# APCBaby8_UIBoard.net
KiCad netlist of a schematic drawn in EAGLE
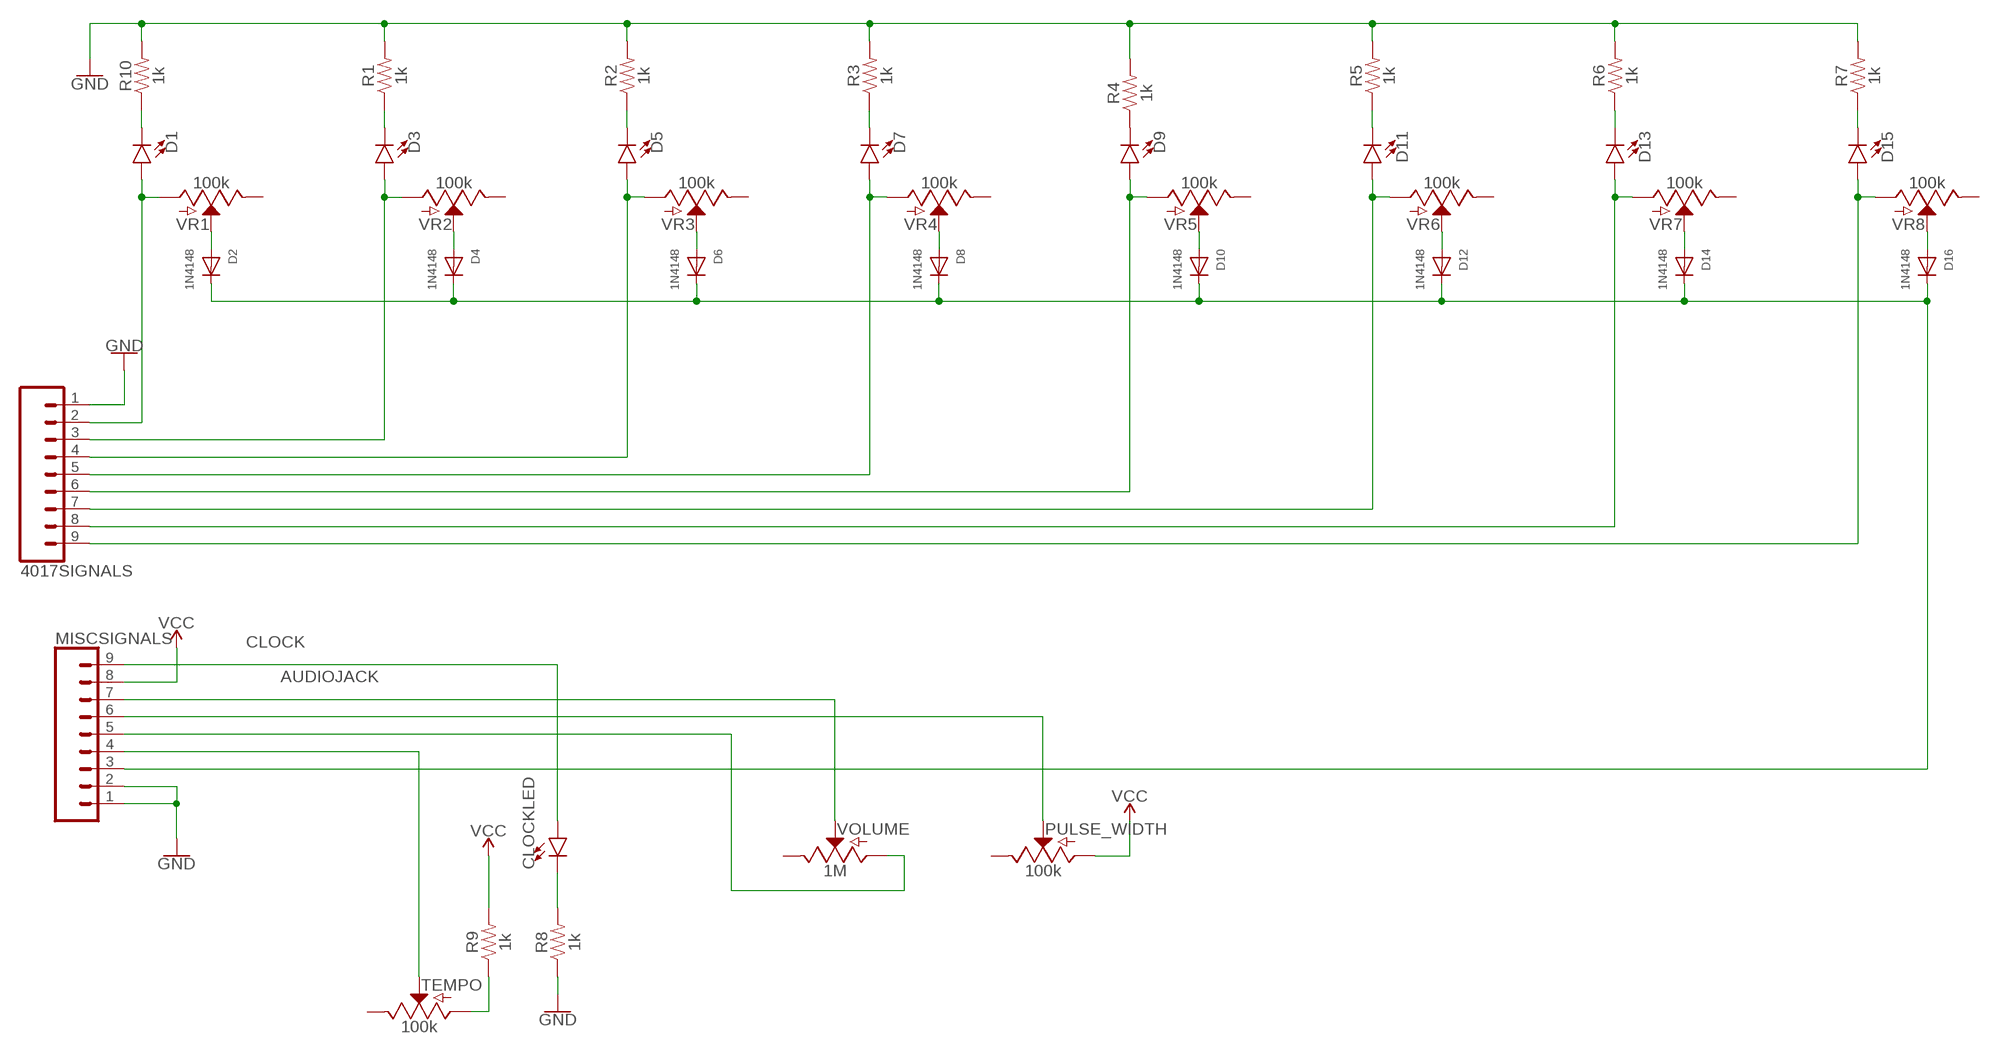
[diagram p0: schematic, sheet 1]

(export (version "E")
  (design (tool "Eeschema 10.0.6"))
  (components
    (comp (ref "4017SIGNALS")
      (value "CONN_09LONGPADS")
      (footprint "eagle-import:1X09_LONGPADS")
      (libsource (lib "eagle-import") (part "CONN_09LONGPADS"))
    )
    (comp (ref "CLOCKLED")
      (value "LED-3MM-NO_SILK")
      (footprint "eagle-import:LED_3MM-NS")
      (libsource (lib "eagle-import") (part "LED-3MM-NO_SILK"))
    )
    (comp (ref "D1")
      (value "LED-3MM-NO_SILK")
      (footprint "eagle-import:LED_3MM-NS")
      (libsource (lib "eagle-import") (part "LED-3MM-NO_SILK"))
    )
    (comp (ref "D2")
      (value "1N4148")
      (footprint "eagle-import:DO-1N4148")
      (libsource (lib "eagle-import") (part "DIODEDO-1N4148"))
    )
    (comp (ref "D3")
      (value "LED-3MM-NO_SILK")
      (footprint "eagle-import:LED_3MM-NS")
      (libsource (lib "eagle-import") (part "LED-3MM-NO_SILK"))
    )
    (comp (ref "D4")
      (value "1N4148")
      (footprint "eagle-import:DO-1N4148")
      (libsource (lib "eagle-import") (part "DIODEDO-1N4148"))
    )
    (comp (ref "D5")
      (value "LED-3MM-NO_SILK")
      (footprint "eagle-import:LED_3MM-NS")
      (libsource (lib "eagle-import") (part "LED-3MM-NO_SILK"))
    )
    (comp (ref "D6")
      (value "1N4148")
      (footprint "eagle-import:DO-1N4148")
      (libsource (lib "eagle-import") (part "DIODEDO-1N4148"))
    )
    (comp (ref "D7")
      (value "LED-3MM-NO_SILK")
      (footprint "eagle-import:LED_3MM-NS")
      (libsource (lib "eagle-import") (part "LED-3MM-NO_SILK"))
    )
    (comp (ref "D8")
      (value "1N4148")
      (footprint "eagle-import:DO-1N4148")
      (libsource (lib "eagle-import") (part "DIODEDO-1N4148"))
    )
    (comp (ref "D9")
      (value "LED-3MM-NO_SILK")
      (footprint "eagle-import:LED_3MM-NS")
      (libsource (lib "eagle-import") (part "LED-3MM-NO_SILK"))
    )
    (comp (ref "D10")
      (value "1N4148")
      (footprint "eagle-import:DO-1N4148")
      (libsource (lib "eagle-import") (part "DIODEDO-1N4148"))
    )
    (comp (ref "D11")
      (value "LED-3MM-NO_SILK")
      (footprint "eagle-import:LED_3MM-NS")
      (libsource (lib "eagle-import") (part "LED-3MM-NO_SILK"))
    )
    (comp (ref "D12")
      (value "1N4148")
      (footprint "eagle-import:DO-1N4148")
      (libsource (lib "eagle-import") (part "DIODEDO-1N4148"))
    )
    (comp (ref "D13")
      (value "LED-3MM-NO_SILK")
      (footprint "eagle-import:LED_3MM-NS")
      (libsource (lib "eagle-import") (part "LED-3MM-NO_SILK"))
    )
    (comp (ref "D14")
      (value "1N4148")
      (footprint "eagle-import:DO-1N4148")
      (libsource (lib "eagle-import") (part "DIODEDO-1N4148"))
    )
    (comp (ref "D15")
      (value "LED-3MM-NO_SILK")
      (footprint "eagle-import:LED_3MM-NS")
      (libsource (lib "eagle-import") (part "LED-3MM-NO_SILK"))
    )
    (comp (ref "D16")
      (value "1N4148")
      (footprint "eagle-import:DO-1N4148")
      (libsource (lib "eagle-import") (part "DIODEDO-1N4148"))
    )
    (comp (ref "MISCSIGNALS")
      (value "CONN_09LONGPADS")
      (footprint "eagle-import:1X09_LONGPADS")
      (libsource (lib "eagle-import") (part "CONN_09LONGPADS"))
    )
    (comp (ref "PULSE_WIDTH")
      (value "100k")
      (footprint "eagle-import:POT-PTH-ALPS")
      (libsource (lib "eagle-import") (part "POTENTIOMETER-PTH-9MM-1/20W-20%"))
    )
    (comp (ref "R1")
      (value "1k")
      (footprint "eagle-import:0805")
      (libsource (lib "eagle-import") (part "0.22OHM-0805-1/4W-1%"))
    )
    (comp (ref "R2")
      (value "1k")
      (footprint "eagle-import:0805")
      (libsource (lib "eagle-import") (part "0.22OHM-0805-1/4W-1%"))
    )
    (comp (ref "R3")
      (value "1k")
      (footprint "eagle-import:0805")
      (libsource (lib "eagle-import") (part "0.22OHM-0805-1/4W-1%"))
    )
    (comp (ref "R4")
      (value "1k")
      (footprint "eagle-import:0805")
      (libsource (lib "eagle-import") (part "0.22OHM-0805-1/4W-1%"))
    )
    (comp (ref "R5")
      (value "1k")
      (footprint "eagle-import:0805")
      (libsource (lib "eagle-import") (part "0.22OHM-0805-1/4W-1%"))
    )
    (comp (ref "R6")
      (value "1k")
      (footprint "eagle-import:0805")
      (libsource (lib "eagle-import") (part "0.22OHM-0805-1/4W-1%"))
    )
    (comp (ref "R7")
      (value "1k")
      (footprint "eagle-import:0805")
      (libsource (lib "eagle-import") (part "0.22OHM-0805-1/4W-1%"))
    )
    (comp (ref "R8")
      (value "1k")
      (footprint "eagle-import:0805")
      (libsource (lib "eagle-import") (part "0.22OHM-0805-1/4W-1%"))
    )
    (comp (ref "R9")
      (value "1k")
      (footprint "eagle-import:0805")
      (libsource (lib "eagle-import") (part "0.22OHM-0805-1/4W-1%"))
    )
    (comp (ref "R10")
      (value "1k")
      (footprint "eagle-import:0805")
      (libsource (lib "eagle-import") (part "0.22OHM-0805-1/4W-1%"))
    )
    (comp (ref "TEMPO")
      (value "100k")
      (footprint "eagle-import:POT-PTH-ALPS")
      (libsource (lib "eagle-import") (part "POTENTIOMETER-PTH-9MM-1/20W-20%"))
    )
    (comp (ref "VOLUME")
      (value "1M")
      (footprint "eagle-import:POT-PTH-ALPS")
      (libsource (lib "eagle-import") (part "POTENTIOMETER-PTH-9MM-1/20W-20%"))
    )
    (comp (ref "VR1")
      (value "100k")
      (footprint "eagle-import:POT-PTH-ALPS")
      (libsource (lib "eagle-import") (part "POTENTIOMETER-PTH-9MM-1/20W-20%"))
    )
    (comp (ref "VR2")
      (value "100k")
      (footprint "eagle-import:POT-PTH-ALPS")
      (libsource (lib "eagle-import") (part "POTENTIOMETER-PTH-9MM-1/20W-20%"))
    )
    (comp (ref "VR3")
      (value "100k")
      (footprint "eagle-import:POT-PTH-ALPS")
      (libsource (lib "eagle-import") (part "POTENTIOMETER-PTH-9MM-1/20W-20%"))
    )
    (comp (ref "VR4")
      (value "100k")
      (footprint "eagle-import:POT-PTH-ALPS")
      (libsource (lib "eagle-import") (part "POTENTIOMETER-PTH-9MM-1/20W-20%"))
    )
    (comp (ref "VR5")
      (value "100k")
      (footprint "eagle-import:POT-PTH-ALPS")
      (libsource (lib "eagle-import") (part "POTENTIOMETER-PTH-9MM-1/20W-20%"))
    )
    (comp (ref "VR6")
      (value "100k")
      (footprint "eagle-import:POT-PTH-ALPS")
      (libsource (lib "eagle-import") (part "POTENTIOMETER-PTH-9MM-1/20W-20%"))
    )
    (comp (ref "VR7")
      (value "100k")
      (footprint "eagle-import:POT-PTH-ALPS")
      (libsource (lib "eagle-import") (part "POTENTIOMETER-PTH-9MM-1/20W-20%"))
    )
    (comp (ref "VR8")
      (value "100k")
      (footprint "eagle-import:POT-PTH-ALPS")
      (libsource (lib "eagle-import") (part "POTENTIOMETER-PTH-9MM-1/20W-20%"))
    )
  )
  (nets
    (net (code "1") (name "/AUDIOJACK") (class "Default")
      (node (ref "MISCSIGNALS") (pin "7") (pinfunction "7_7") (pintype "passive"))
      (node (ref "VOLUME") (pin "P$2") (pinfunction "S_P$2") (pintype "passive"))
    )
    (net (code "2") (name "/CLOCK") (class "Default")
      (node (ref "CLOCKLED") (pin "A") (pinfunction "A_A") (pintype "passive"))
      (node (ref "MISCSIGNALS") (pin "9") (pinfunction "9_9") (pintype "passive"))
    )
    (net (code "3") (name "GND") (class "Default")
      (node (ref "4017SIGNALS") (pin "1") (pinfunction "1_1") (pintype "passive"))
      (node (ref "MISCSIGNALS") (pin "1") (pinfunction "1_1") (pintype "passive"))
      (node (ref "MISCSIGNALS") (pin "2") (pinfunction "2_2") (pintype "passive"))
      (node (ref "R1") (pin "2") (pinfunction "2_2") (pintype "passive"))
      (node (ref "R10") (pin "2") (pinfunction "2_2") (pintype "passive"))
      (node (ref "R2") (pin "2") (pinfunction "2_2") (pintype "passive"))
      (node (ref "R3") (pin "2") (pinfunction "2_2") (pintype "passive"))
      (node (ref "R4") (pin "2") (pinfunction "2_2") (pintype "passive"))
      (node (ref "R5") (pin "2") (pinfunction "2_2") (pintype "passive"))
      (node (ref "R6") (pin "2") (pinfunction "2_2") (pintype "passive"))
      (node (ref "R7") (pin "2") (pinfunction "2_2") (pintype "passive"))
      (node (ref "R8") (pin "1") (pinfunction "1_1") (pintype "passive"))
    )
    (net (code "4") (name "Net-(CLOCKLED-C)") (class "Default")
      (node (ref "CLOCKLED") (pin "K") (pinfunction "C_K") (pintype "passive"))
      (node (ref "R8") (pin "2") (pinfunction "2_2") (pintype "passive"))
    )
    (net (code "5") (name "Net-(D1-C)") (class "Default")
      (node (ref "D1") (pin "K") (pinfunction "C_K") (pintype "passive"))
      (node (ref "R10") (pin "1") (pinfunction "1_1") (pintype "passive"))
    )
    (net (code "6") (name "Net-(D3-C)") (class "Default")
      (node (ref "D3") (pin "K") (pinfunction "C_K") (pintype "passive"))
      (node (ref "R1") (pin "1") (pinfunction "1_1") (pintype "passive"))
    )
    (net (code "7") (name "Net-(D5-C)") (class "Default")
      (node (ref "D5") (pin "K") (pinfunction "C_K") (pintype "passive"))
      (node (ref "R2") (pin "1") (pinfunction "1_1") (pintype "passive"))
    )
    (net (code "8") (name "Net-(D7-C)") (class "Default")
      (node (ref "D7") (pin "K") (pinfunction "C_K") (pintype "passive"))
      (node (ref "R3") (pin "1") (pinfunction "1_1") (pintype "passive"))
    )
    (net (code "9") (name "Net-(D9-C)") (class "Default")
      (node (ref "D9") (pin "K") (pinfunction "C_K") (pintype "passive"))
      (node (ref "R4") (pin "1") (pinfunction "1_1") (pintype "passive"))
    )
    (net (code "10") (name "Net-(D10-PadC)") (class "Default")
      (node (ref "D10") (pin "C") (pinfunction "C_C") (pintype "passive"))
      (node (ref "D12") (pin "C") (pinfunction "C_C") (pintype "passive"))
      (node (ref "D14") (pin "C") (pinfunction "C_C") (pintype "passive"))
      (node (ref "D16") (pin "C") (pinfunction "C_C") (pintype "passive"))
      (node (ref "D2") (pin "C") (pinfunction "C_C") (pintype "passive"))
      (node (ref "D4") (pin "C") (pinfunction "C_C") (pintype "passive"))
      (node (ref "D6") (pin "C") (pinfunction "C_C") (pintype "passive"))
      (node (ref "D8") (pin "C") (pinfunction "C_C") (pintype "passive"))
      (node (ref "MISCSIGNALS") (pin "3") (pinfunction "3_3") (pintype "passive"))
    )
    (net (code "11") (name "Net-(D11-C)") (class "Default")
      (node (ref "D11") (pin "K") (pinfunction "C_K") (pintype "passive"))
      (node (ref "R5") (pin "1") (pinfunction "1_1") (pintype "passive"))
    )
    (net (code "12") (name "Net-(D13-C)") (class "Default")
      (node (ref "D13") (pin "K") (pinfunction "C_K") (pintype "passive"))
      (node (ref "R6") (pin "1") (pinfunction "1_1") (pintype "passive"))
    )
    (net (code "13") (name "Net-(D15-C)") (class "Default")
      (node (ref "D15") (pin "K") (pinfunction "C_K") (pintype "passive"))
      (node (ref "R7") (pin "1") (pinfunction "1_1") (pintype "passive"))
    )
    (net (code "14") (name "Net-(PULSE_WIDTH-S)") (class "Default")
      (node (ref "MISCSIGNALS") (pin "6") (pinfunction "6_6") (pintype "passive"))
      (node (ref "PULSE_WIDTH") (pin "P$2") (pinfunction "S_P$2") (pintype "passive"))
    )
    (net (code "15") (name "Net-(TEMPO-A)") (class "Default")
      (node (ref "R9") (pin "1") (pinfunction "1_1") (pintype "passive"))
      (node (ref "TEMPO") (pin "P$3") (pinfunction "A_P$3") (pintype "passive"))
    )
    (net (code "16") (name "Net-(TEMPO-S)") (class "Default")
      (node (ref "MISCSIGNALS") (pin "4") (pinfunction "4_4") (pintype "passive"))
      (node (ref "TEMPO") (pin "P$2") (pinfunction "S_P$2") (pintype "passive"))
    )
    (net (code "17") (name "Net-(VOLUME-A)") (class "Default")
      (node (ref "MISCSIGNALS") (pin "5") (pinfunction "5_5") (pintype "passive"))
      (node (ref "VOLUME") (pin "P$3") (pinfunction "A_P$3") (pintype "passive"))
    )
    (net (code "18") (name "Net-(VR1-A)") (class "Default")
      (node (ref "4017SIGNALS") (pin "2") (pinfunction "2_2") (pintype "passive"))
      (node (ref "D1") (pin "A") (pinfunction "A_A") (pintype "passive"))
      (node (ref "VR1") (pin "P$3") (pinfunction "A_P$3") (pintype "passive"))
    )
    (net (code "19") (name "Net-(VR1-S)") (class "Default")
      (node (ref "D2") (pin "A") (pinfunction "A_A") (pintype "passive"))
      (node (ref "VR1") (pin "P$2") (pinfunction "S_P$2") (pintype "passive"))
    )
    (net (code "20") (name "Net-(VR2-A)") (class "Default")
      (node (ref "4017SIGNALS") (pin "3") (pinfunction "3_3") (pintype "passive"))
      (node (ref "D3") (pin "A") (pinfunction "A_A") (pintype "passive"))
      (node (ref "VR2") (pin "P$3") (pinfunction "A_P$3") (pintype "passive"))
    )
    (net (code "21") (name "Net-(VR2-S)") (class "Default")
      (node (ref "D4") (pin "A") (pinfunction "A_A") (pintype "passive"))
      (node (ref "VR2") (pin "P$2") (pinfunction "S_P$2") (pintype "passive"))
    )
    (net (code "22") (name "Net-(VR3-A)") (class "Default")
      (node (ref "4017SIGNALS") (pin "4") (pinfunction "4_4") (pintype "passive"))
      (node (ref "D5") (pin "A") (pinfunction "A_A") (pintype "passive"))
      (node (ref "VR3") (pin "P$3") (pinfunction "A_P$3") (pintype "passive"))
    )
    (net (code "23") (name "Net-(VR3-S)") (class "Default")
      (node (ref "D6") (pin "A") (pinfunction "A_A") (pintype "passive"))
      (node (ref "VR3") (pin "P$2") (pinfunction "S_P$2") (pintype "passive"))
    )
    (net (code "24") (name "Net-(VR4-A)") (class "Default")
      (node (ref "4017SIGNALS") (pin "5") (pinfunction "5_5") (pintype "passive"))
      (node (ref "D7") (pin "A") (pinfunction "A_A") (pintype "passive"))
      (node (ref "VR4") (pin "P$3") (pinfunction "A_P$3") (pintype "passive"))
    )
    (net (code "25") (name "Net-(VR4-S)") (class "Default")
      (node (ref "D8") (pin "A") (pinfunction "A_A") (pintype "passive"))
      (node (ref "VR4") (pin "P$2") (pinfunction "S_P$2") (pintype "passive"))
    )
    (net (code "26") (name "Net-(VR5-A)") (class "Default")
      (node (ref "4017SIGNALS") (pin "6") (pinfunction "6_6") (pintype "passive"))
      (node (ref "D9") (pin "A") (pinfunction "A_A") (pintype "passive"))
      (node (ref "VR5") (pin "P$3") (pinfunction "A_P$3") (pintype "passive"))
    )
    (net (code "27") (name "Net-(VR5-S)") (class "Default")
      (node (ref "D10") (pin "A") (pinfunction "A_A") (pintype "passive"))
      (node (ref "VR5") (pin "P$2") (pinfunction "S_P$2") (pintype "passive"))
    )
    (net (code "28") (name "Net-(VR6-A)") (class "Default")
      (node (ref "4017SIGNALS") (pin "7") (pinfunction "7_7") (pintype "passive"))
      (node (ref "D11") (pin "A") (pinfunction "A_A") (pintype "passive"))
      (node (ref "VR6") (pin "P$3") (pinfunction "A_P$3") (pintype "passive"))
    )
    (net (code "29") (name "Net-(VR6-S)") (class "Default")
      (node (ref "D12") (pin "A") (pinfunction "A_A") (pintype "passive"))
      (node (ref "VR6") (pin "P$2") (pinfunction "S_P$2") (pintype "passive"))
    )
    (net (code "30") (name "Net-(VR7-A)") (class "Default")
      (node (ref "4017SIGNALS") (pin "8") (pinfunction "8_8") (pintype "passive"))
      (node (ref "D13") (pin "A") (pinfunction "A_A") (pintype "passive"))
      (node (ref "VR7") (pin "P$3") (pinfunction "A_P$3") (pintype "passive"))
    )
    (net (code "31") (name "Net-(VR7-S)") (class "Default")
      (node (ref "D14") (pin "A") (pinfunction "A_A") (pintype "passive"))
      (node (ref "VR7") (pin "P$2") (pinfunction "S_P$2") (pintype "passive"))
    )
    (net (code "32") (name "Net-(VR8-A)") (class "Default")
      (node (ref "4017SIGNALS") (pin "9") (pinfunction "9_9") (pintype "passive"))
      (node (ref "D15") (pin "A") (pinfunction "A_A") (pintype "passive"))
      (node (ref "VR8") (pin "P$3") (pinfunction "A_P$3") (pintype "passive"))
    )
    (net (code "33") (name "Net-(VR8-S)") (class "Default")
      (node (ref "D16") (pin "A") (pinfunction "A_A") (pintype "passive"))
      (node (ref "VR8") (pin "P$2") (pinfunction "S_P$2") (pintype "passive"))
    )
    (net (code "34") (name "VCC") (class "Default")
      (node (ref "MISCSIGNALS") (pin "8") (pinfunction "8_8") (pintype "passive"))
      (node (ref "PULSE_WIDTH") (pin "P$3") (pinfunction "A_P$3") (pintype "passive"))
      (node (ref "R9") (pin "2") (pinfunction "2_2") (pintype "passive"))
    )
    (net (code "35") (name "unconnected-(PULSE_WIDTH-E-PadP$1)") (class "Default")
      (node (ref "PULSE_WIDTH") (pin "P$1") (pinfunction "E_P$1") (pintype "passive"))
    )
    (net (code "36") (name "unconnected-(TEMPO-E-PadP$1)") (class "Default")
      (node (ref "TEMPO") (pin "P$1") (pinfunction "E_P$1") (pintype "passive"))
    )
    (net (code "37") (name "unconnected-(VOLUME-E-PadP$1)") (class "Default")
      (node (ref "VOLUME") (pin "P$1") (pinfunction "E_P$1") (pintype "passive"))
    )
    (net (code "38") (name "unconnected-(VR1-E-PadP$1)") (class "Default")
      (node (ref "VR1") (pin "P$1") (pinfunction "E_P$1") (pintype "passive"))
    )
    (net (code "39") (name "unconnected-(VR2-E-PadP$1)") (class "Default")
      (node (ref "VR2") (pin "P$1") (pinfunction "E_P$1") (pintype "passive"))
    )
    (net (code "40") (name "unconnected-(VR3-E-PadP$1)") (class "Default")
      (node (ref "VR3") (pin "P$1") (pinfunction "E_P$1") (pintype "passive"))
    )
    (net (code "41") (name "unconnected-(VR4-E-PadP$1)") (class "Default")
      (node (ref "VR4") (pin "P$1") (pinfunction "E_P$1") (pintype "passive"))
    )
    (net (code "42") (name "unconnected-(VR5-E-PadP$1)") (class "Default")
      (node (ref "VR5") (pin "P$1") (pinfunction "E_P$1") (pintype "passive"))
    )
    (net (code "43") (name "unconnected-(VR6-E-PadP$1)") (class "Default")
      (node (ref "VR6") (pin "P$1") (pinfunction "E_P$1") (pintype "passive"))
    )
    (net (code "44") (name "unconnected-(VR7-E-PadP$1)") (class "Default")
      (node (ref "VR7") (pin "P$1") (pinfunction "E_P$1") (pintype "passive"))
    )
    (net (code "45") (name "unconnected-(VR8-E-PadP$1)") (class "Default")
      (node (ref "VR8") (pin "P$1") (pinfunction "E_P$1") (pintype "passive"))
    )
  )
)
